# ECE411_T10_schematic.net
KiCad netlist of a schematic drawn in EAGLE
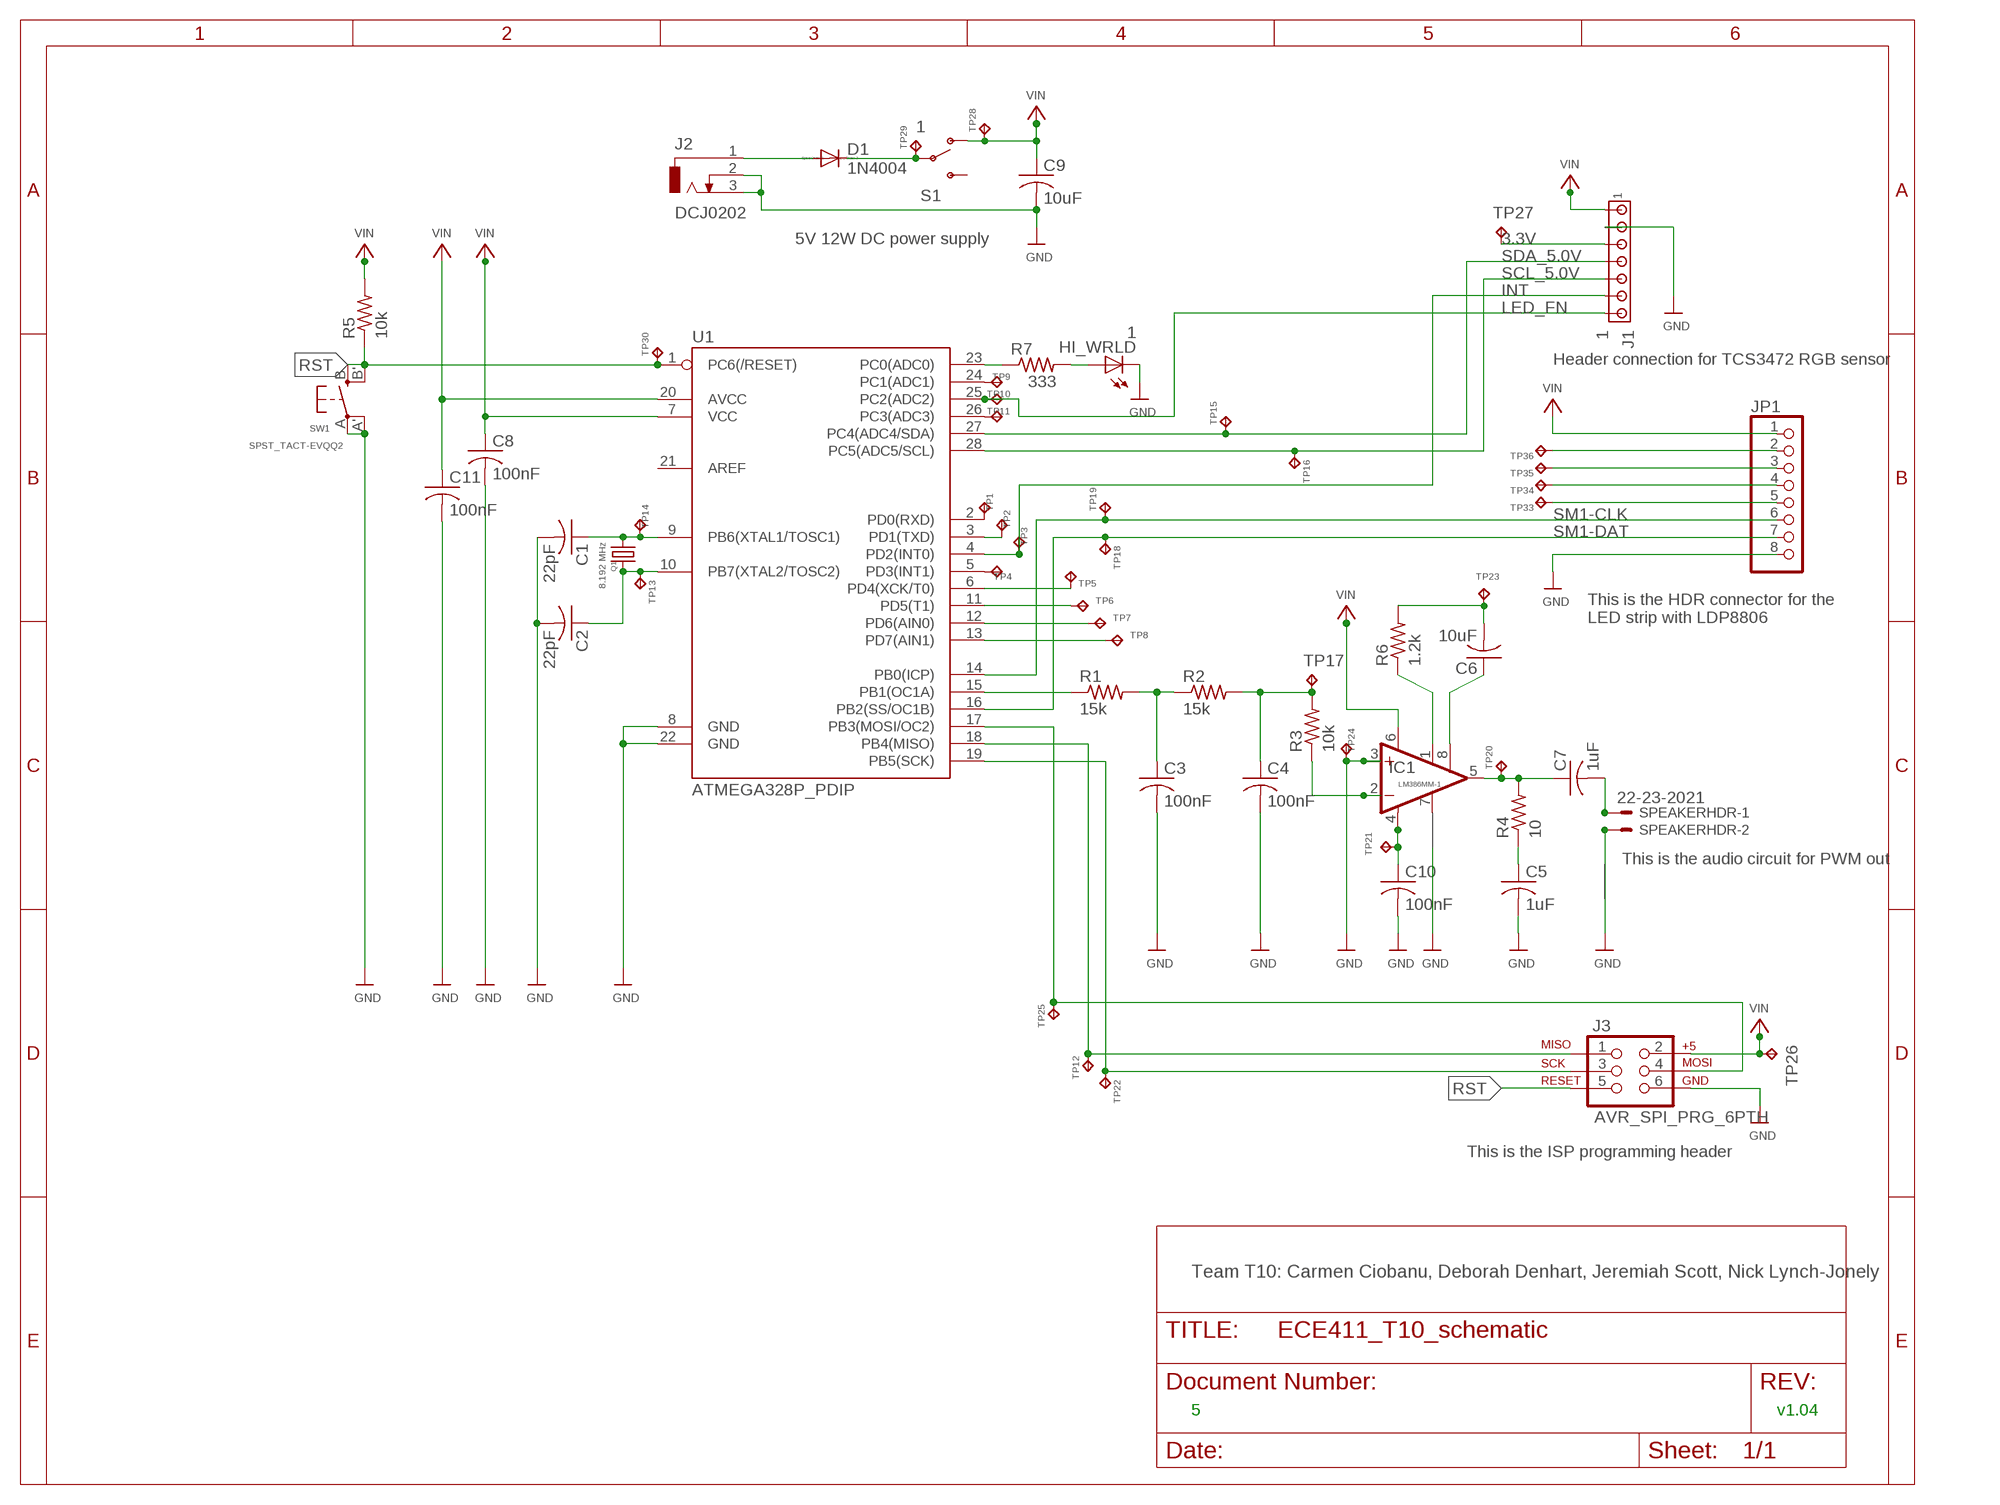
[diagram p0: schematic, sheet 1]

(export (version "E")
  (design (tool "Eeschema 10.0.6"))
  (components
    (comp (ref "C1")
      (value "22pF")
      (footprint "eagle-import:C0805")
      (libsource (lib "eagle-import") (part "resistor_C-USC0805"))
    )
    (comp (ref "C2")
      (value "22pF")
      (footprint "eagle-import:C0805")
      (libsource (lib "eagle-import") (part "resistor_C-USC0805"))
    )
    (comp (ref "C3")
      (value "100nF")
      (footprint "eagle-import:C0805")
      (libsource (lib "eagle-import") (part "resistor_C-USC0805"))
    )
    (comp (ref "C4")
      (value "100nF")
      (footprint "eagle-import:C0805")
      (libsource (lib "eagle-import") (part "resistor_C-USC0805"))
    )
    (comp (ref "C5")
      (value "1uF")
      (footprint "eagle-import:C0805")
      (libsource (lib "eagle-import") (part "resistor_C-USC0805"))
    )
    (comp (ref "C6")
      (value "10uF")
      (footprint "eagle-import:C0805")
      (libsource (lib "eagle-import") (part "resistor_C-USC0805"))
    )
    (comp (ref "C7")
      (value "1uF")
      (footprint "eagle-import:C0805")
      (libsource (lib "eagle-import") (part "resistor_C-USC0805"))
    )
    (comp (ref "C8")
      (value "100nF")
      (footprint "eagle-import:C0805")
      (libsource (lib "eagle-import") (part "resistor_C-USC0805"))
    )
    (comp (ref "C9")
      (value "10uF")
      (footprint "eagle-import:C0805")
      (libsource (lib "eagle-import") (part "resistor_C-USC0805"))
    )
    (comp (ref "C10")
      (value "100nF")
      (footprint "eagle-import:C0805")
      (libsource (lib "eagle-import") (part "resistor_C-USC0805"))
    )
    (comp (ref "C11")
      (value "100nF")
      (footprint "eagle-import:C0805")
      (libsource (lib "eagle-import") (part "C-USC0805"))
    )
    (comp (ref "D1")
      (value "1N4004")
      (footprint "eagle-import:DO41-10")
      (libsource (lib "eagle-import") (part "1N4004"))
    )
    (comp (ref "HI_WRLD")
      (value "1")
      (footprint "eagle-import:SML1206")
      (libsource (lib "eagle-import") (part "LEDSML1206"))
    )
    (comp (ref "IC1")
      (value "LM386MM-1")
      (footprint "eagle-import:MMSOP08")
      (libsource (lib "eagle-import") (part "LM386?-MM1"))
    )
    (comp (ref "J1")
      (value "1")
      (footprint "eagle-import:10X07MTA")
      (libsource (lib "eagle-import") (part "MTA07-100"))
    )
    (comp (ref "J2")
      (value "DCJ0202")
      (footprint "eagle-import:DCJ0202")
      (libsource (lib "eagle-import") (part "DCJ0202"))
    )
    (comp (ref "J3")
      (value "AVR_SPI_PRG_6PTH")
      (footprint "eagle-import:2X3")
      (libsource (lib "eagle-import") (part "AVR_SPI_PRG_6PTH"))
    )
    (comp (ref "JP1")
      (value "PINHD-1X8")
      (footprint "eagle-import:1X08")
      (libsource (lib "eagle-import") (part "PINHD-1X8"))
    )
    (comp (ref "Q1")
      (value "8.192 MHz")
      (footprint "eagle-import:HC49_S")
      (libsource (lib "eagle-import") (part "CRYSTALHC49S"))
    )
    (comp (ref "R1")
      (value "15k")
      (footprint "eagle-import:M0805")
      (libsource (lib "eagle-import") (part "R-US_M0805"))
    )
    (comp (ref "R2")
      (value "15k")
      (footprint "eagle-import:M0805")
      (libsource (lib "eagle-import") (part "R-US_M0805"))
    )
    (comp (ref "R3")
      (value "10k")
      (footprint "eagle-import:M0805")
      (libsource (lib "eagle-import") (part "R-US_M0805"))
    )
    (comp (ref "R4")
      (value "10")
      (footprint "eagle-import:M0805")
      (libsource (lib "eagle-import") (part "R-US_M0805"))
    )
    (comp (ref "R5")
      (value "10k")
      (footprint "eagle-import:M0805")
      (libsource (lib "eagle-import") (part "R-US_M0805"))
    )
    (comp (ref "R6")
      (value "1.2k")
      (footprint "eagle-import:M0805")
      (libsource (lib "eagle-import") (part "R-US_M0805"))
    )
    (comp (ref "R7")
      (value "333")
      (footprint "eagle-import:M0805")
      (libsource (lib "eagle-import") (part "R-US_M0805"))
    )
    (comp (ref "S1")
      (value "1")
      (footprint "eagle-import:SWITCH-SPST-SMD-A")
      (libsource (lib "eagle-import") (part "SWITCH-SPDT-SMD-A"))
    )
    (comp (ref "SPEAKERHDR")
      (value "22-23-2021")
      (footprint "eagle-import:22-23-2021")
      (fields (field (name "MF") "MOLEX"))
      (libsource (lib "eagle-import") (part "22-23-2021"))
    )
    (comp (ref "SW1")
      (value "SPST_TACT-EVQQ2")
      (footprint "eagle-import:EVQ-Q2")
      (libsource (lib "eagle-import") (part "SPST_TACT-EVQQ2"))
    )
    (comp (ref "TP1")
      (value "TPB1,27")
      (footprint "eagle-import:B1,27")
      (libsource (lib "eagle-import") (part "TPB1,27"))
    )
    (comp (ref "TP2")
      (value "TPB1,27")
      (footprint "eagle-import:B1,27")
      (libsource (lib "eagle-import") (part "TPB1,27"))
    )
    (comp (ref "TP3")
      (value "TPB1,27")
      (footprint "eagle-import:B1,27")
      (libsource (lib "eagle-import") (part "TPB1,27"))
    )
    (comp (ref "TP4")
      (value "TPB1,27")
      (footprint "eagle-import:B1,27")
      (libsource (lib "eagle-import") (part "TPB1,27"))
    )
    (comp (ref "TP5")
      (value "TPB1,27")
      (footprint "eagle-import:B1,27")
      (libsource (lib "eagle-import") (part "TPB1,27"))
    )
    (comp (ref "TP6")
      (value "TPB1,27")
      (footprint "eagle-import:B1,27")
      (libsource (lib "eagle-import") (part "TPB1,27"))
    )
    (comp (ref "TP7")
      (value "TPB1,27")
      (footprint "eagle-import:B1,27")
      (libsource (lib "eagle-import") (part "TPB1,27"))
    )
    (comp (ref "TP8")
      (value "TPB1,27")
      (footprint "eagle-import:B1,27")
      (libsource (lib "eagle-import") (part "TPB1,27"))
    )
    (comp (ref "TP9")
      (value "TPB1,27")
      (footprint "eagle-import:B1,27")
      (libsource (lib "eagle-import") (part "TPB1,27"))
    )
    (comp (ref "TP10")
      (value "TPB1,27")
      (footprint "eagle-import:B1,27")
      (libsource (lib "eagle-import") (part "TPB1,27"))
    )
    (comp (ref "TP11")
      (value "TPB1,27")
      (footprint "eagle-import:B1,27")
      (libsource (lib "eagle-import") (part "TPB1,27"))
    )
    (comp (ref "TP12")
      (value "TPB1,27")
      (footprint "eagle-import:B1,27")
      (libsource (lib "eagle-import") (part "TPB1,27"))
    )
    (comp (ref "TP13")
      (value "TPB1,27")
      (footprint "eagle-import:B1,27")
      (libsource (lib "eagle-import") (part "TPB1,27"))
    )
    (comp (ref "TP14")
      (value "TPB1,27")
      (footprint "eagle-import:B1,27")
      (libsource (lib "eagle-import") (part "TPB1,27"))
    )
    (comp (ref "TP15")
      (value "TPB1,27")
      (footprint "eagle-import:B1,27")
      (libsource (lib "eagle-import") (part "TPB1,27"))
    )
    (comp (ref "TP16")
      (value "TPB1,27")
      (footprint "eagle-import:B1,27")
      (libsource (lib "eagle-import") (part "TPB1,27"))
    )
    (comp (ref "TP17")
      (value "TPB1,27")
      (footprint "eagle-import:B1,27")
      (libsource (lib "eagle-import") (part "TPB1,27"))
    )
    (comp (ref "TP18")
      (value "TPB1,27")
      (footprint "eagle-import:B1,27")
      (libsource (lib "eagle-import") (part "TPB1,27"))
    )
    (comp (ref "TP19")
      (value "TPB1,27")
      (footprint "eagle-import:B1,27")
      (libsource (lib "eagle-import") (part "TPB1,27"))
    )
    (comp (ref "TP20")
      (value "TPB1,27")
      (footprint "eagle-import:B1,27")
      (libsource (lib "eagle-import") (part "TPB1,27"))
    )
    (comp (ref "TP21")
      (value "TPB1,27")
      (footprint "eagle-import:B1,27")
      (libsource (lib "eagle-import") (part "TPB1,27"))
    )
    (comp (ref "TP22")
      (value "TPB1,27")
      (footprint "eagle-import:B1,27")
      (libsource (lib "eagle-import") (part "TPB1,27"))
    )
    (comp (ref "TP23")
      (value "TPB1,27")
      (footprint "eagle-import:B1,27")
      (libsource (lib "eagle-import") (part "TPB1,27"))
    )
    (comp (ref "TP24")
      (value "TPB1,27")
      (footprint "eagle-import:B1,27")
      (libsource (lib "eagle-import") (part "TPB1,27"))
    )
    (comp (ref "TP25")
      (value "TPB1,27")
      (footprint "eagle-import:B1,27")
      (libsource (lib "eagle-import") (part "TPB1,27"))
    )
    (comp (ref "TP26")
      (value "TPB1,27")
      (footprint "eagle-import:B1,27")
      (libsource (lib "eagle-import") (part "TPB1,27"))
    )
    (comp (ref "TP27")
      (value "TPB1,27")
      (footprint "eagle-import:B1,27")
      (libsource (lib "eagle-import") (part "TPB1,27"))
    )
    (comp (ref "TP28")
      (value "TPB1,27")
      (footprint "eagle-import:B1,27")
      (libsource (lib "eagle-import") (part "TPB1,27"))
    )
    (comp (ref "TP29")
      (value "TPB1,27")
      (footprint "eagle-import:B1,27")
      (libsource (lib "eagle-import") (part "TPB1,27"))
    )
    (comp (ref "TP30")
      (value "TPB1,27")
      (footprint "eagle-import:B1,27")
      (libsource (lib "eagle-import") (part "TPB1,27"))
    )
    (comp (ref "TP33")
      (value "TPB1,27")
      (footprint "eagle-import:B1,27")
      (libsource (lib "eagle-import") (part "TPB1,27"))
    )
    (comp (ref "TP34")
      (value "TPB1,27")
      (footprint "eagle-import:B1,27")
      (libsource (lib "eagle-import") (part "TPB1,27"))
    )
    (comp (ref "TP35")
      (value "TPB1,27")
      (footprint "eagle-import:B1,27")
      (libsource (lib "eagle-import") (part "TPB1,27"))
    )
    (comp (ref "TP36")
      (value "TPB1,27")
      (footprint "eagle-import:B1,27")
      (libsource (lib "eagle-import") (part "TPB1,27"))
    )
    (comp (ref "U1")
      (value "ATMEGA328P_PDIP")
      (footprint "eagle-import:DIL28-3")
      (libsource (lib "eagle-import") (part "ATMEGA328P_PDIP"))
    )
  )
  (nets
    (net (code "1") (name "/3.3V") (class "Default")
      (node (ref "J1") (pin "3") (pinfunction "3_3") (pintype "passive"))
      (node (ref "TP27") (pin "TP") (pinfunction "TP_TP") (pintype "input"))
    )
    (net (code "2") (name "/INT") (class "Default")
      (node (ref "J1") (pin "6") (pinfunction "6_6") (pintype "passive"))
      (node (ref "TP3") (pin "TP") (pinfunction "TP_TP") (pintype "input"))
      (node (ref "U1") (pin "4") (pinfunction "PD2(INT0)_4") (pintype "bidirectional"))
    )
    (net (code "3") (name "/LED_FN") (class "Default")
      (node (ref "J1") (pin "7") (pinfunction "7_7") (pintype "passive"))
      (node (ref "TP10") (pin "TP") (pinfunction "TP_TP") (pintype "input"))
      (node (ref "U1") (pin "25") (pinfunction "PC2(ADC2)_25") (pintype "bidirectional"))
    )
    (net (code "4") (name "/SCL_5.0V") (class "Default")
      (node (ref "J1") (pin "5") (pinfunction "5_5") (pintype "passive"))
      (node (ref "TP16") (pin "TP") (pinfunction "TP_TP") (pintype "input"))
      (node (ref "U1") (pin "28") (pinfunction "PC5(ADC5/SCL)_28") (pintype "bidirectional"))
    )
    (net (code "5") (name "/SDA_5.0V") (class "Default")
      (node (ref "J1") (pin "4") (pinfunction "4_4") (pintype "passive"))
      (node (ref "TP15") (pin "TP") (pinfunction "TP_TP") (pintype "input"))
      (node (ref "U1") (pin "27") (pinfunction "PC4(ADC4/SDA)_27") (pintype "bidirectional"))
    )
    (net (code "6") (name "/SM1-CLK") (class "Default")
      (node (ref "JP1") (pin "6") (pinfunction "6_6") (pintype "passive"))
      (node (ref "TP19") (pin "TP") (pinfunction "TP_TP") (pintype "input"))
      (node (ref "U1") (pin "14") (pinfunction "PB0(ICP)_14") (pintype "bidirectional"))
    )
    (net (code "7") (name "/SM1-DAT") (class "Default")
      (node (ref "JP1") (pin "7") (pinfunction "7_7") (pintype "passive"))
      (node (ref "TP18") (pin "TP") (pinfunction "TP_TP") (pintype "input"))
      (node (ref "U1") (pin "16") (pinfunction "PB2(SS/OC1B)_16") (pintype "bidirectional"))
    )
    (net (code "8") (name "GND") (class "Default")
      (node (ref "C1") (pin "2") (pinfunction "2_2") (pintype "passive"))
      (node (ref "C10") (pin "2") (pinfunction "2_2") (pintype "passive"))
      (node (ref "C11") (pin "2") (pinfunction "2_2") (pintype "passive"))
      (node (ref "C2") (pin "2") (pinfunction "2_2") (pintype "passive"))
      (node (ref "C3") (pin "2") (pinfunction "2_2") (pintype "passive"))
      (node (ref "C4") (pin "2") (pinfunction "2_2") (pintype "passive"))
      (node (ref "C5") (pin "2") (pinfunction "2_2") (pintype "passive"))
      (node (ref "C8") (pin "2") (pinfunction "2_2") (pintype "passive"))
      (node (ref "C9") (pin "2") (pinfunction "2_2") (pintype "passive"))
      (node (ref "HI_WRLD") (pin "C") (pinfunction "C_C") (pintype "passive"))
      (node (ref "IC1") (pin "3") (pinfunction "+IN_3") (pintype "input"))
      (node (ref "IC1") (pin "7") (pinfunction "BYPASS_7") (pintype "passive"))
      (node (ref "J1") (pin "2") (pinfunction "2_2") (pintype "passive"))
      (node (ref "J2") (pin "2") (pinfunction "2_2") (pintype "passive"))
      (node (ref "J2") (pin "3") (pinfunction "3_3") (pintype "passive"))
      (node (ref "J3") (pin "6") (pinfunction "6_6") (pintype "passive"))
      (node (ref "JP1") (pin "8") (pinfunction "8_8") (pintype "passive"))
      (node (ref "SPEAKERHDR") (pin "2") (pinfunction "S_2") (pintype "passive"))
      (node (ref "SW1") (pin "A") (pinfunction "P_A") (pintype "passive"))
      (node (ref "SW1") (pin "A'") (pinfunction "P1_A'") (pintype "passive"))
      (node (ref "TP24") (pin "TP") (pinfunction "TP_TP") (pintype "input"))
      (node (ref "U1") (pin "22") (pinfunction "GND_22") (pintype "bidirectional"))
      (node (ref "U1") (pin "8") (pinfunction "GND_8") (pintype "bidirectional"))
    )
    (net (code "9") (name "Net-(C3-Pad1)") (class "Default")
      (node (ref "C3") (pin "1") (pinfunction "1_1") (pintype "passive"))
      (node (ref "R1") (pin "2") (pinfunction "2_2") (pintype "passive"))
      (node (ref "R2") (pin "1") (pinfunction "1_1") (pintype "passive"))
    )
    (net (code "10") (name "Net-(C4-Pad1)") (class "Default")
      (node (ref "C4") (pin "1") (pinfunction "1_1") (pintype "passive"))
      (node (ref "R2") (pin "2") (pinfunction "2_2") (pintype "passive"))
      (node (ref "R3") (pin "2") (pinfunction "2_2") (pintype "passive"))
      (node (ref "TP17") (pin "TP") (pinfunction "TP_TP") (pintype "input"))
    )
    (net (code "11") (name "Net-(C5-Pad1)") (class "Default")
      (node (ref "C5") (pin "1") (pinfunction "1_1") (pintype "passive"))
      (node (ref "R4") (pin "1") (pinfunction "1_1") (pintype "passive"))
    )
    (net (code "12") (name "Net-(C6-Pad1)") (class "Default")
      (node (ref "C6") (pin "1") (pinfunction "1_1") (pintype "passive"))
      (node (ref "IC1") (pin "8") (pinfunction "GAIN_8") (pintype "passive"))
    )
    (net (code "13") (name "Net-(C6-Pad2)") (class "Default")
      (node (ref "C6") (pin "2") (pinfunction "2_2") (pintype "passive"))
      (node (ref "R6") (pin "2") (pinfunction "2_2") (pintype "passive"))
      (node (ref "TP23") (pin "TP") (pinfunction "TP_TP") (pintype "input"))
    )
    (net (code "14") (name "Net-(D1-PadA)") (class "Default")
      (node (ref "D1") (pin "A") (pinfunction "A_A") (pintype "passive"))
      (node (ref "J2") (pin "1") (pinfunction "1_1") (pintype "passive"))
    )
    (net (code "15") (name "Net-(HI_WRLD-PadA)") (class "Default")
      (node (ref "HI_WRLD") (pin "A") (pinfunction "A_A") (pintype "passive"))
      (node (ref "R7") (pin "2") (pinfunction "2_2") (pintype "passive"))
    )
    (net (code "16") (name "Net-(IC1--IN)") (class "Default")
      (node (ref "IC1") (pin "2") (pinfunction "-IN_2") (pintype "input"))
      (node (ref "R3") (pin "1") (pinfunction "1_1") (pintype "passive"))
    )
    (net (code "17") (name "Net-(IC1-GAIN-Pad1)") (class "Default")
      (node (ref "IC1") (pin "1") (pinfunction "GAIN_1") (pintype "passive"))
      (node (ref "R6") (pin "1") (pinfunction "1_1") (pintype "passive"))
    )
    (net (code "18") (name "Net-(IC1-GND)") (class "Default")
      (node (ref "C10") (pin "1") (pinfunction "1_1") (pintype "passive"))
      (node (ref "IC1") (pin "4") (pinfunction "GND_4") (pintype "power_in"))
      (node (ref "TP21") (pin "TP") (pinfunction "TP_TP") (pintype "input"))
    )
    (net (code "19") (name "Net-(IC1-OUT)") (class "Default")
      (node (ref "C7") (pin "1") (pinfunction "1_1") (pintype "passive"))
      (node (ref "IC1") (pin "5") (pinfunction "OUT_5") (pintype "output"))
      (node (ref "R4") (pin "2") (pinfunction "2_2") (pintype "passive"))
      (node (ref "TP20") (pin "TP") (pinfunction "TP_TP") (pintype "input"))
    )
    (net (code "20") (name "Net-(JP1-Pad2)") (class "Default")
      (node (ref "JP1") (pin "2") (pinfunction "2_2") (pintype "passive"))
      (node (ref "TP36") (pin "TP") (pinfunction "TP_TP") (pintype "input"))
    )
    (net (code "21") (name "Net-(JP1-Pad3)") (class "Default")
      (node (ref "JP1") (pin "3") (pinfunction "3_3") (pintype "passive"))
      (node (ref "TP35") (pin "TP") (pinfunction "TP_TP") (pintype "input"))
    )
    (net (code "22") (name "Net-(JP1-Pad4)") (class "Default")
      (node (ref "JP1") (pin "4") (pinfunction "4_4") (pintype "passive"))
      (node (ref "TP34") (pin "TP") (pinfunction "TP_TP") (pintype "input"))
    )
    (net (code "23") (name "Net-(JP1-Pad5)") (class "Default")
      (node (ref "JP1") (pin "5") (pinfunction "5_5") (pintype "passive"))
      (node (ref "TP33") (pin "TP") (pinfunction "TP_TP") (pintype "input"))
    )
    (net (code "24") (name "Net-(S1-P)") (class "Default")
      (node (ref "D1") (pin "C") (pinfunction "C_C") (pintype "passive"))
      (node (ref "S1") (pin "2") (pinfunction "P_2") (pintype "passive"))
      (node (ref "TP29") (pin "TP") (pinfunction "TP_TP") (pintype "input"))
    )
    (net (code "25") (name "Net-(SPEAKERHDRA-S)") (class "Default")
      (node (ref "C7") (pin "2") (pinfunction "2_2") (pintype "passive"))
      (node (ref "SPEAKERHDR") (pin "1") (pinfunction "S_1") (pintype "passive"))
    )
    (net (code "26") (name "Net-(U1-PB1(OC1A))") (class "Default")
      (node (ref "R1") (pin "1") (pinfunction "1_1") (pintype "passive"))
      (node (ref "U1") (pin "15") (pinfunction "PB1(OC1A)_15") (pintype "bidirectional"))
    )
    (net (code "27") (name "Net-(U1-PB3(MOSI{slash}OC2))") (class "Default")
      (node (ref "J3") (pin "4") (pinfunction "4_4") (pintype "passive"))
      (node (ref "TP25") (pin "TP") (pinfunction "TP_TP") (pintype "input"))
      (node (ref "U1") (pin "17") (pinfunction "PB3(MOSI/OC2)_17") (pintype "bidirectional"))
    )
    (net (code "28") (name "Net-(U1-PB4(MISO))") (class "Default")
      (node (ref "J3") (pin "1") (pinfunction "1_1") (pintype "passive"))
      (node (ref "TP12") (pin "TP") (pinfunction "TP_TP") (pintype "input"))
      (node (ref "U1") (pin "18") (pinfunction "PB4(MISO)_18") (pintype "bidirectional"))
    )
    (net (code "29") (name "Net-(U1-PB5(SCK))") (class "Default")
      (node (ref "J3") (pin "3") (pinfunction "3_3") (pintype "passive"))
      (node (ref "TP22") (pin "TP") (pinfunction "TP_TP") (pintype "input"))
      (node (ref "U1") (pin "19") (pinfunction "PB5(SCK)_19") (pintype "bidirectional"))
    )
    (net (code "30") (name "Net-(U1-PB6(XTAL1{slash}TOSC1))") (class "Default")
      (node (ref "C1") (pin "1") (pinfunction "1_1") (pintype "passive"))
      (node (ref "Q1") (pin "2") (pinfunction "2_2") (pintype "passive"))
      (node (ref "TP14") (pin "TP") (pinfunction "TP_TP") (pintype "input"))
      (node (ref "U1") (pin "9") (pinfunction "PB6(XTAL1/TOSC1)_9") (pintype "bidirectional"))
    )
    (net (code "31") (name "Net-(U1-PB7(XTAL2{slash}TOSC2))") (class "Default")
      (node (ref "C2") (pin "1") (pinfunction "1_1") (pintype "passive"))
      (node (ref "Q1") (pin "1") (pinfunction "1_1") (pintype "passive"))
      (node (ref "TP13") (pin "TP") (pinfunction "TP_TP") (pintype "input"))
      (node (ref "U1") (pin "10") (pinfunction "PB7(XTAL2/TOSC2)_10") (pintype "bidirectional"))
    )
    (net (code "32") (name "Net-(U1-PC0(ADC0))") (class "Default")
      (node (ref "R7") (pin "1") (pinfunction "1_1") (pintype "passive"))
      (node (ref "U1") (pin "23") (pinfunction "PC0(ADC0)_23") (pintype "bidirectional"))
    )
    (net (code "33") (name "Net-(U1-PC1(ADC1))") (class "Default")
      (node (ref "TP9") (pin "TP") (pinfunction "TP_TP") (pintype "input"))
      (node (ref "U1") (pin "24") (pinfunction "PC1(ADC1)_24") (pintype "bidirectional"))
    )
    (net (code "34") (name "Net-(U1-PC3(ADC3))") (class "Default")
      (node (ref "TP11") (pin "TP") (pinfunction "TP_TP") (pintype "input"))
      (node (ref "U1") (pin "26") (pinfunction "PC3(ADC3)_26") (pintype "bidirectional"))
    )
    (net (code "35") (name "Net-(U1-PD0(RXD))") (class "Default")
      (node (ref "TP1") (pin "TP") (pinfunction "TP_TP") (pintype "input"))
      (node (ref "U1") (pin "2") (pinfunction "PD0(RXD)_2") (pintype "bidirectional"))
    )
    (net (code "36") (name "Net-(U1-PD1(TXD))") (class "Default")
      (node (ref "TP2") (pin "TP") (pinfunction "TP_TP") (pintype "input"))
      (node (ref "U1") (pin "3") (pinfunction "PD1(TXD)_3") (pintype "bidirectional"))
    )
    (net (code "37") (name "Net-(U1-PD3(INT1))") (class "Default")
      (node (ref "TP4") (pin "TP") (pinfunction "TP_TP") (pintype "input"))
      (node (ref "U1") (pin "5") (pinfunction "PD3(INT1)_5") (pintype "bidirectional"))
    )
    (net (code "38") (name "Net-(U1-PD4(XCK{slash}T0))") (class "Default")
      (node (ref "TP5") (pin "TP") (pinfunction "TP_TP") (pintype "input"))
      (node (ref "U1") (pin "6") (pinfunction "PD4(XCK/T0)_6") (pintype "bidirectional"))
    )
    (net (code "39") (name "Net-(U1-PD5(T1))") (class "Default")
      (node (ref "TP6") (pin "TP") (pinfunction "TP_TP") (pintype "input"))
      (node (ref "U1") (pin "11") (pinfunction "PD5(T1)_11") (pintype "bidirectional"))
    )
    (net (code "40") (name "Net-(U1-PD6(AIN0))") (class "Default")
      (node (ref "TP7") (pin "TP") (pinfunction "TP_TP") (pintype "input"))
      (node (ref "U1") (pin "12") (pinfunction "PD6(AIN0)_12") (pintype "bidirectional"))
    )
    (net (code "41") (name "Net-(U1-PD7(AIN1))") (class "Default")
      (node (ref "TP8") (pin "TP") (pinfunction "TP_TP") (pintype "input"))
      (node (ref "U1") (pin "13") (pinfunction "PD7(AIN1)_13") (pintype "bidirectional"))
    )
    (net (code "42") (name "RST") (class "Default")
      (node (ref "J3") (pin "5") (pinfunction "5_5") (pintype "passive"))
      (node (ref "R5") (pin "1") (pinfunction "1_1") (pintype "passive"))
      (node (ref "SW1") (pin "B") (pinfunction "S_B") (pintype "passive"))
      (node (ref "SW1") (pin "B'") (pinfunction "S1_B'") (pintype "passive"))
      (node (ref "TP30") (pin "TP") (pinfunction "TP_TP") (pintype "input"))
      (node (ref "U1") (pin "1") (pinfunction "PC6(/RESET)_1") (pintype "bidirectional"))
    )
    (net (code "43") (name "VIN") (class "Default")
      (node (ref "C11") (pin "1") (pinfunction "1_1") (pintype "passive"))
      (node (ref "C8") (pin "1") (pinfunction "1_1") (pintype "passive"))
      (node (ref "C9") (pin "1") (pinfunction "1_1") (pintype "passive"))
      (node (ref "IC1") (pin "6") (pinfunction "VS_6") (pintype "power_in"))
      (node (ref "J1") (pin "1") (pinfunction "1_1") (pintype "passive"))
      (node (ref "J3") (pin "2") (pinfunction "2_2") (pintype "passive"))
      (node (ref "JP1") (pin "1") (pinfunction "1_1") (pintype "passive"))
      (node (ref "R5") (pin "2") (pinfunction "2_2") (pintype "passive"))
      (node (ref "S1") (pin "1") (pinfunction "O_1") (pintype "passive"))
      (node (ref "TP26") (pin "TP") (pinfunction "TP_TP") (pintype "input"))
      (node (ref "TP28") (pin "TP") (pinfunction "TP_TP") (pintype "input"))
      (node (ref "U1") (pin "20") (pinfunction "AVCC_20") (pintype "bidirectional"))
      (node (ref "U1") (pin "7") (pinfunction "VCC_7") (pintype "bidirectional"))
    )
    (net (code "44") (name "unconnected-(S1-S-Pad3)") (class "Default")
      (node (ref "S1") (pin "3") (pinfunction "S_3") (pintype "passive"))
    )
    (net (code "45") (name "unconnected-(U1-AREF-Pad21)") (class "Default")
      (node (ref "U1") (pin "21") (pinfunction "AREF_21") (pintype "bidirectional"))
    )
  )
)
